# main.net
KiCad netlist of a schematic drawn in EAGLE
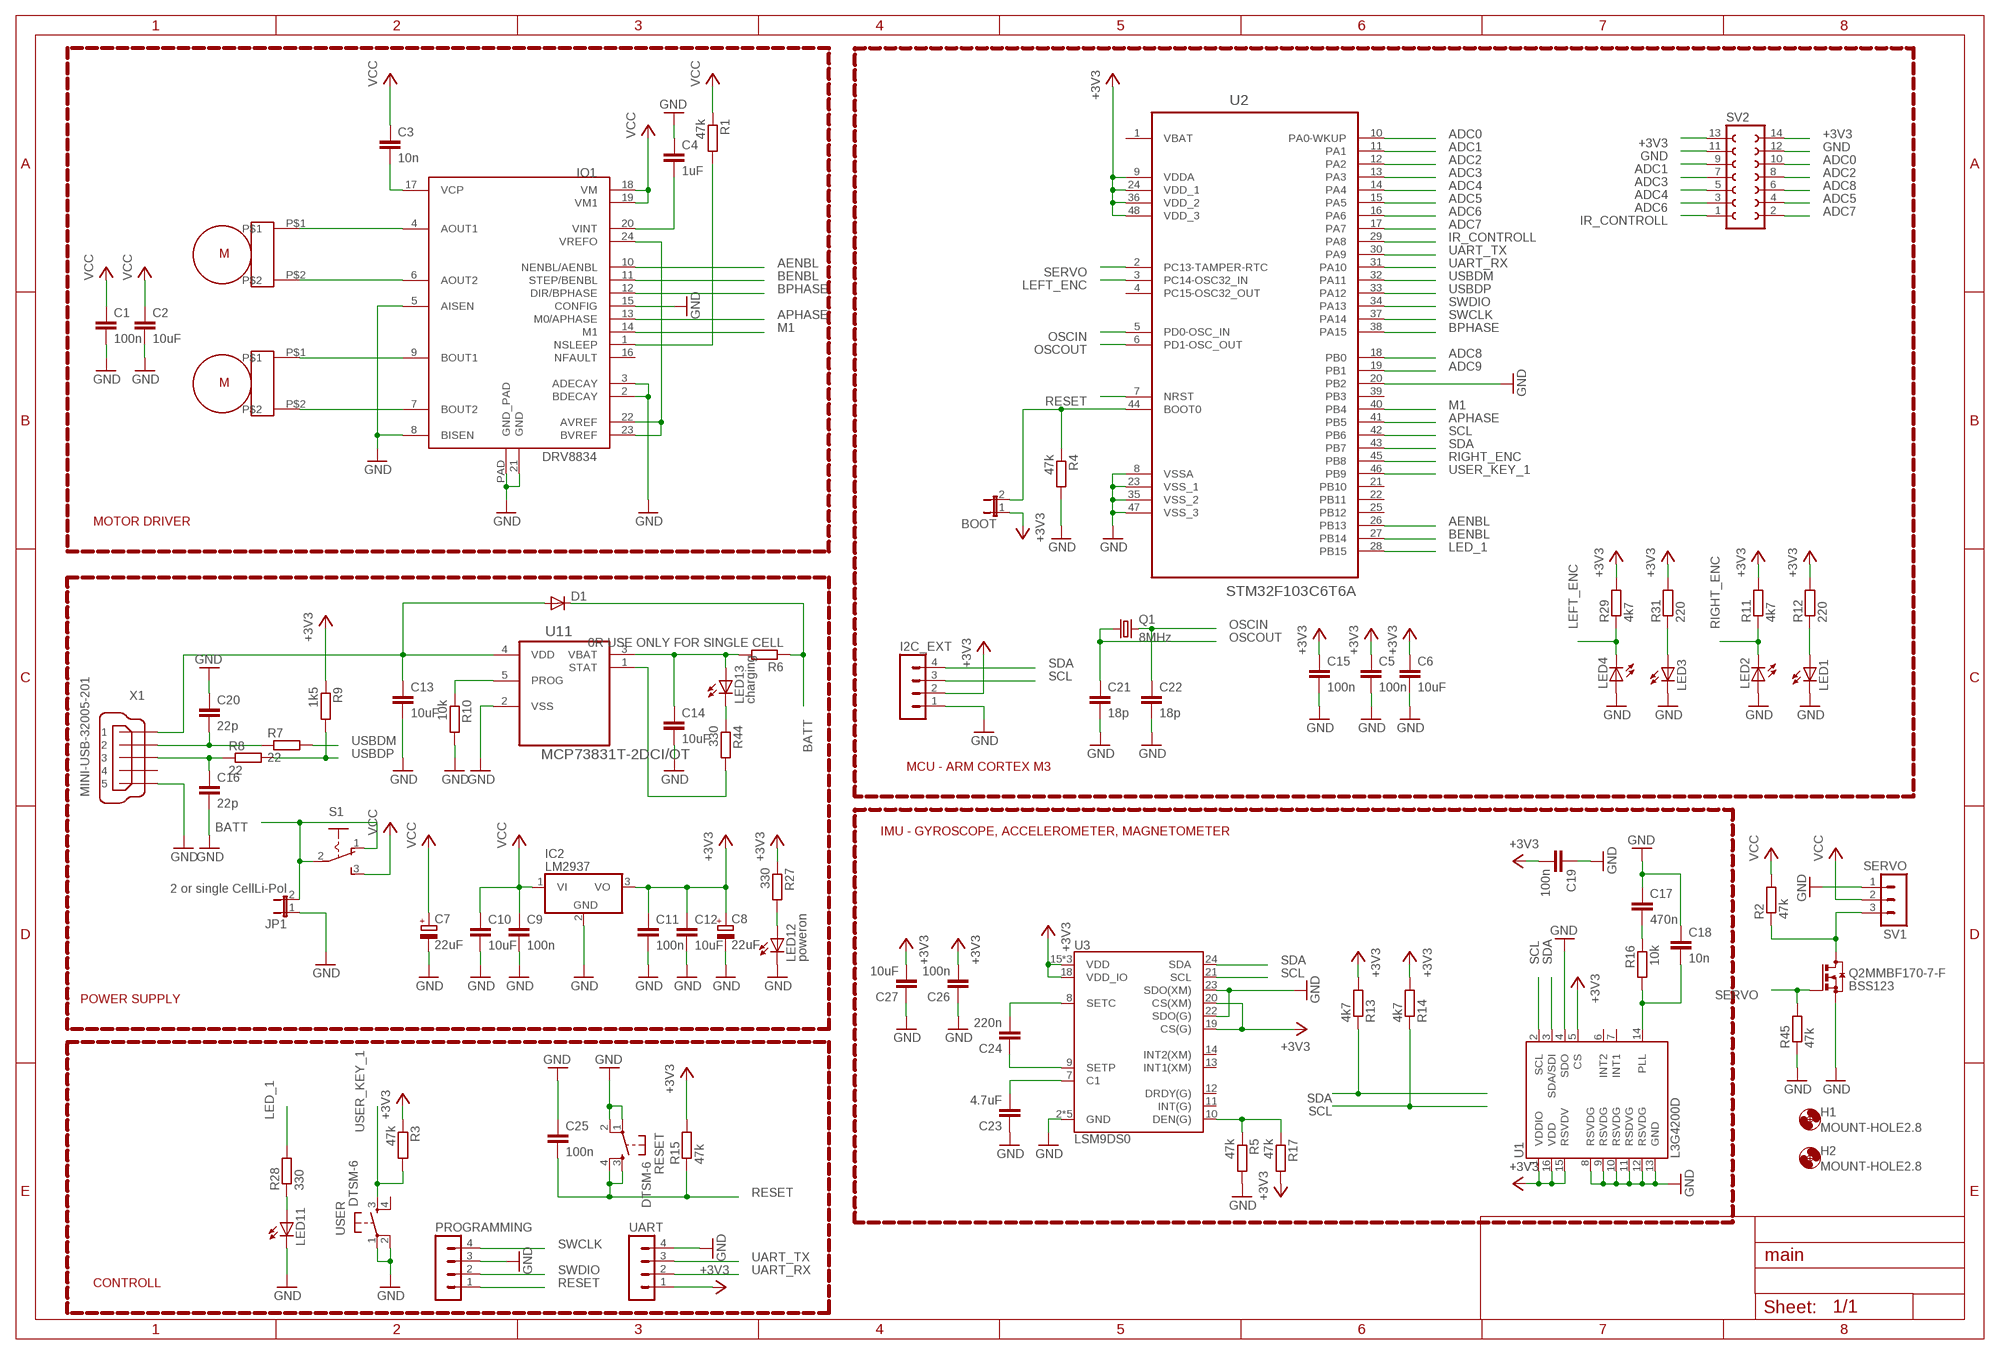
[diagram p0: schematic, sheet 1, part 1 of 2]
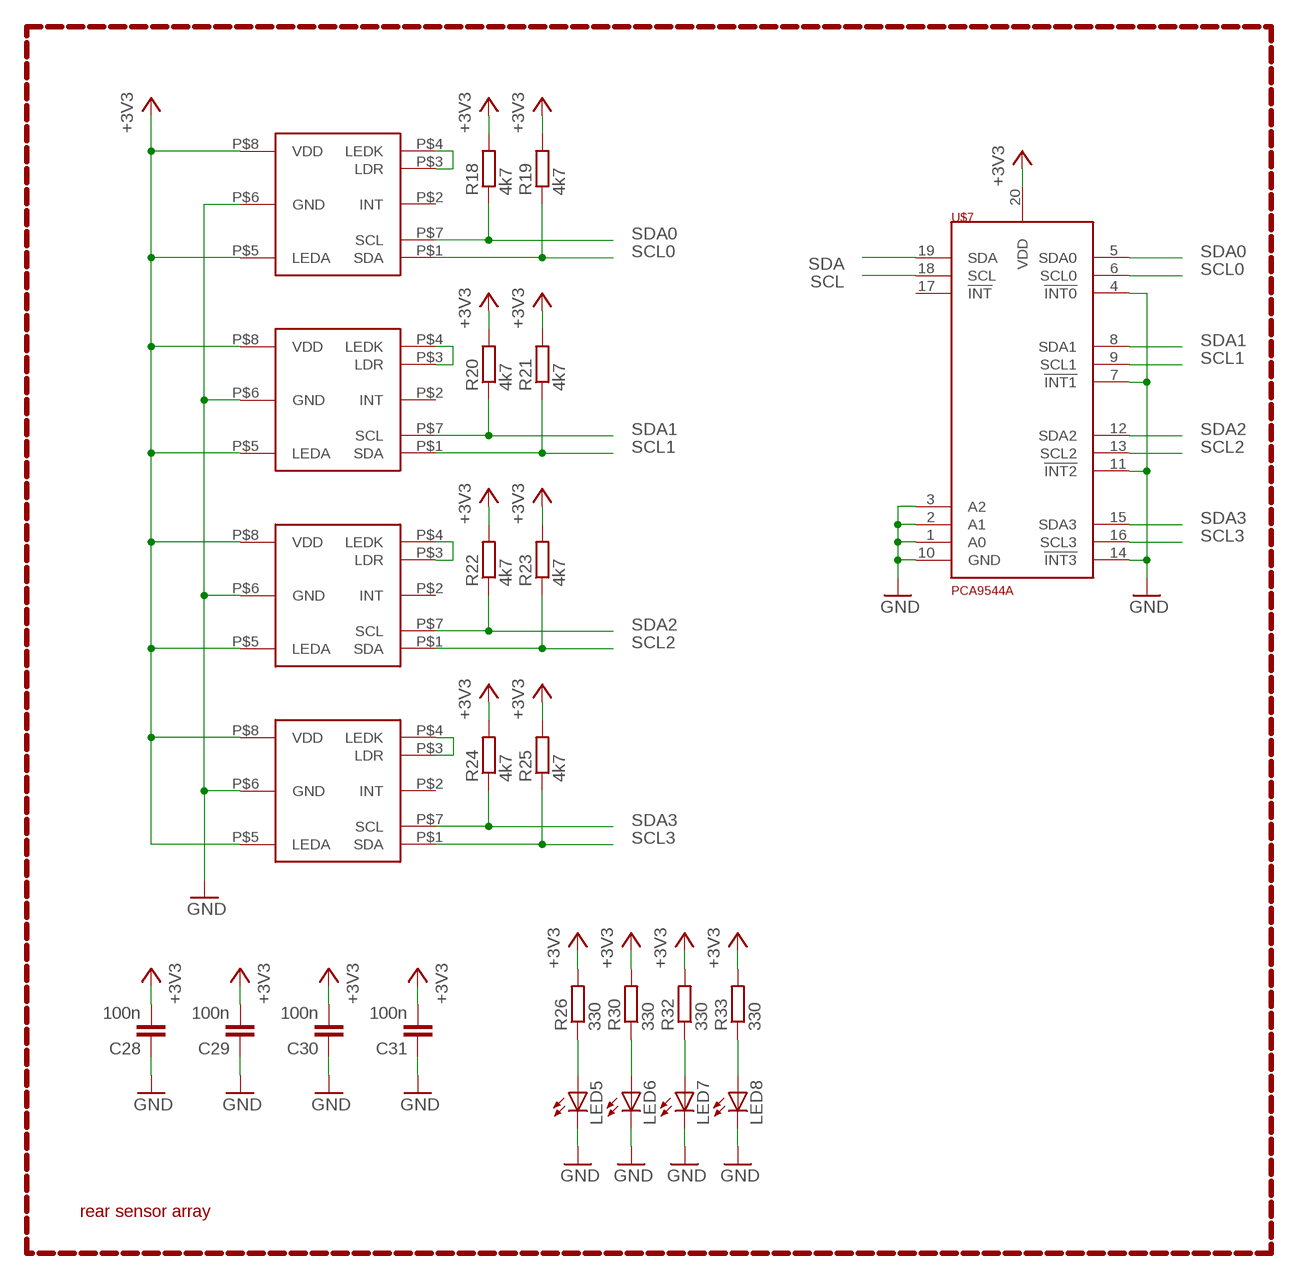
[diagram p1: schematic, sheet 1, part 2 of 2]

(export (version "E")
  (design (tool "Eeschema 10.0.6"))
  (components
    (comp (ref "BOOT")
      (value "JP1E")
      (footprint "eagle-import:JP1")
      (libsource (lib "eagle-import") (part "JP1E"))
    )
    (comp (ref "C1")
      (value "100n")
      (footprint "eagle-import:C1206")
      (libsource (lib "eagle-import") (part "C-EUC1206"))
    )
    (comp (ref "C2")
      (value "10uF")
      (footprint "eagle-import:C1206")
      (libsource (lib "eagle-import") (part "C-EUC1206"))
    )
    (comp (ref "C3")
      (value "10n")
      (footprint "eagle-import:C1206")
      (libsource (lib "eagle-import") (part "C-EUC1206"))
    )
    (comp (ref "C4")
      (value "1uF")
      (footprint "eagle-import:C1206")
      (libsource (lib "eagle-import") (part "C-EUC1206"))
    )
    (comp (ref "C5")
      (value "100n")
      (footprint "eagle-import:C0805")
      (libsource (lib "eagle-import") (part "C-EUC0805"))
    )
    (comp (ref "C6")
      (value "10uF")
      (footprint "eagle-import:C0805")
      (libsource (lib "eagle-import") (part "C-EUC0805"))
    )
    (comp (ref "C7")
      (value "22uF")
      (footprint "eagle-import:153CLV-0505")
      (libsource (lib "eagle-import") (part "CPOL-EU153CLV-0505"))
    )
    (comp (ref "C8")
      (value "22uF")
      (footprint "eagle-import:153CLV-0505")
      (libsource (lib "eagle-import") (part "CPOL-EU153CLV-0505"))
    )
    (comp (ref "C9")
      (value "100n")
      (footprint "eagle-import:C0805")
      (libsource (lib "eagle-import") (part "C-EUC0805"))
    )
    (comp (ref "C10")
      (value "10uF")
      (footprint "eagle-import:C0805")
      (libsource (lib "eagle-import") (part "C-EUC0805"))
    )
    (comp (ref "C11")
      (value "100n")
      (footprint "eagle-import:C0805")
      (libsource (lib "eagle-import") (part "C-EUC0805"))
    )
    (comp (ref "C12")
      (value "10uF")
      (footprint "eagle-import:C0805")
      (libsource (lib "eagle-import") (part "C-EUC0805"))
    )
    (comp (ref "C13")
      (value "10uF")
      (footprint "eagle-import:C0805")
      (libsource (lib "eagle-import") (part "C-EUC0805"))
    )
    (comp (ref "C14")
      (value "10uF")
      (footprint "eagle-import:C0805")
      (libsource (lib "eagle-import") (part "C-EUC0805"))
    )
    (comp (ref "C15")
      (value "100n")
      (footprint "eagle-import:C0805")
      (libsource (lib "eagle-import") (part "C-EUC0805"))
    )
    (comp (ref "C16")
      (value "22p")
      (footprint "eagle-import:C0805")
      (libsource (lib "eagle-import") (part "C-EUC0805"))
    )
    (comp (ref "C17")
      (value "470n")
      (footprint "eagle-import:C0805")
      (libsource (lib "eagle-import") (part "C-EUC0805"))
    )
    (comp (ref "C18")
      (value "10n")
      (footprint "eagle-import:C0805")
      (libsource (lib "eagle-import") (part "C-EUC0805"))
    )
    (comp (ref "C19")
      (value "100n")
      (footprint "eagle-import:C0805")
      (libsource (lib "eagle-import") (part "C-EUC0805"))
    )
    (comp (ref "C20")
      (value "22p")
      (footprint "eagle-import:C0805")
      (libsource (lib "eagle-import") (part "C-EUC0805"))
    )
    (comp (ref "C21")
      (value "18p")
      (footprint "eagle-import:C0805")
      (libsource (lib "eagle-import") (part "C-EUC0805"))
    )
    (comp (ref "C22")
      (value "18p")
      (footprint "eagle-import:C0805")
      (libsource (lib "eagle-import") (part "C-EUC0805"))
    )
    (comp (ref "C23")
      (value "4.7uF")
      (footprint "eagle-import:C0805")
      (libsource (lib "eagle-import") (part "C-EUC0805"))
    )
    (comp (ref "C24")
      (value "220n")
      (footprint "eagle-import:C0805")
      (libsource (lib "eagle-import") (part "C-EUC0805"))
    )
    (comp (ref "C25")
      (value "100n")
      (footprint "eagle-import:C0805")
      (libsource (lib "eagle-import") (part "C-EUC0805"))
    )
    (comp (ref "C26")
      (value "100n")
      (footprint "eagle-import:C0805")
      (libsource (lib "eagle-import") (part "C-EUC0805"))
    )
    (comp (ref "C27")
      (value "10uF")
      (footprint "eagle-import:C0805")
      (libsource (lib "eagle-import") (part "C-EUC0805"))
    )
    (comp (ref "C28")
      (value "100n")
      (footprint "eagle-import:C0805")
      (libsource (lib "eagle-import") (part "C-EUC0805"))
    )
    (comp (ref "C29")
      (value "100n")
      (footprint "eagle-import:C0805")
      (libsource (lib "eagle-import") (part "C-EUC0805"))
    )
    (comp (ref "C30")
      (value "100n")
      (footprint "eagle-import:C0805")
      (libsource (lib "eagle-import") (part "C-EUC0805"))
    )
    (comp (ref "C31")
      (value "100n")
      (footprint "eagle-import:C0805")
      (libsource (lib "eagle-import") (part "C-EUC0805"))
    )
    (comp (ref "D1")
      (value "DIODE-SMB")
      (footprint "eagle-import:SMB")
      (libsource (lib "eagle-import") (part "DIODE-SMB"))
    )
    (comp (ref "H1")
      (value "MOUNT-HOLE2.8")
      (footprint "eagle-import:2,8")
      (libsource (lib "eagle-import") (part "MOUNT-HOLE2.8"))
    )
    (comp (ref "H2")
      (value "MOUNT-HOLE2.8")
      (footprint "eagle-import:2,8")
      (libsource (lib "eagle-import") (part "MOUNT-HOLE2.8"))
    )
    (comp (ref "I2C_EXT")
      (value "MA04-1")
      (footprint "eagle-import:MA04-1")
      (libsource (lib "eagle-import") (part "MA04-1"))
    )
    (comp (ref "IC2")
      (value "LM2937")
      (footprint "eagle-import:TO263-3")
      (libsource (lib "eagle-import") (part "LM2937"))
    )
    (comp (ref "IO1")
      (value "DRV8834")
      (footprint "eagle-import:DRV8834_PCK")
      (libsource (lib "eagle-import") (part "DRV8834"))
    )
    (comp (ref "JP1")
      (value "2 or single CellLi-Pol")
      (footprint "eagle-import:JP1")
      (libsource (lib "eagle-import") (part "JP1E"))
    )
    (comp (ref "LED1")
      (value "LEDCHIPLED_1206")
      (footprint "eagle-import:CHIPLED_1206")
      (libsource (lib "eagle-import") (part "LEDCHIPLED_1206"))
    )
    (comp (ref "LED2")
      (value "LEDCHIPLED_1206")
      (footprint "eagle-import:CHIPLED_1206")
      (libsource (lib "eagle-import") (part "LEDCHIPLED_1206"))
    )
    (comp (ref "LED3")
      (value "LEDCHIPLED_1206")
      (footprint "eagle-import:CHIPLED_1206")
      (libsource (lib "eagle-import") (part "LEDCHIPLED_1206"))
    )
    (comp (ref "LED4")
      (value "LEDCHIPLED_1206")
      (footprint "eagle-import:CHIPLED_1206")
      (libsource (lib "eagle-import") (part "LEDCHIPLED_1206"))
    )
    (comp (ref "LED5")
      (value "LEDCHIPLED_1206")
      (footprint "eagle-import:CHIPLED_1206")
      (libsource (lib "eagle-import") (part "LEDCHIPLED_1206"))
    )
    (comp (ref "LED6")
      (value "LEDCHIPLED_1206")
      (footprint "eagle-import:CHIPLED_1206")
      (libsource (lib "eagle-import") (part "LEDCHIPLED_1206"))
    )
    (comp (ref "LED7")
      (value "LEDCHIPLED_1206")
      (footprint "eagle-import:CHIPLED_1206")
      (libsource (lib "eagle-import") (part "LEDCHIPLED_1206"))
    )
    (comp (ref "LED8")
      (value "LEDCHIPLED_1206")
      (footprint "eagle-import:CHIPLED_1206")
      (libsource (lib "eagle-import") (part "LEDCHIPLED_1206"))
    )
    (comp (ref "LED11")
      (value "LEDCHIPLED_1206")
      (footprint "eagle-import:CHIPLED_1206")
      (libsource (lib "eagle-import") (part "LEDCHIPLED_1206"))
    )
    (comp (ref "LED12")
      (value "poweron")
      (footprint "eagle-import:CHIPLED_1206")
      (libsource (lib "eagle-import") (part "LEDCHIPLED_1206"))
    )
    (comp (ref "LED13")
      (value "charging")
      (footprint "eagle-import:CHIPLED_1206")
      (libsource (lib "eagle-import") (part "LEDCHIPLED_1206"))
    )
    (comp (ref "PROGRAMMING")
      (value "MA04-1")
      (footprint "eagle-import:MA04-1")
      (libsource (lib "eagle-import") (part "MA04-1"))
    )
    (comp (ref "Q1")
      (value "8MHz")
      (footprint "eagle-import:CTS406")
      (libsource (lib "eagle-import") (part "CRYSTALCTS406"))
    )
    (comp (ref "Q2MMBF170-7-F")
      (value "BSS123")
      (footprint "eagle-import:SOT23")
      (libsource (lib "eagle-import") (part "BSS123"))
    )
    (comp (ref "R1")
      (value "47k")
      (footprint "eagle-import:M1206")
      (libsource (lib "eagle-import") (part "R-EU_M1206"))
    )
    (comp (ref "R2")
      (value "47k")
      (footprint "eagle-import:M0805")
      (libsource (lib "eagle-import") (part "R-EU_M0805"))
    )
    (comp (ref "R3")
      (value "47k")
      (footprint "eagle-import:M0805")
      (libsource (lib "eagle-import") (part "R-EU_M0805"))
    )
    (comp (ref "R4")
      (value "47k")
      (footprint "eagle-import:M0805")
      (libsource (lib "eagle-import") (part "R-EU_M0805"))
    )
    (comp (ref "R5")
      (value "47k")
      (footprint "eagle-import:M0805")
      (libsource (lib "eagle-import") (part "R-EU_M0805"))
    )
    (comp (ref "R6")
      (value "0R USE ONLY FOR SINGLE CELL")
      (footprint "eagle-import:M1206")
      (libsource (lib "eagle-import") (part "R-EU_M1206"))
    )
    (comp (ref "R7")
      (value "22")
      (footprint "eagle-import:M0805")
      (libsource (lib "eagle-import") (part "R-EU_M0805"))
    )
    (comp (ref "R8")
      (value "22")
      (footprint "eagle-import:M0805")
      (libsource (lib "eagle-import") (part "R-EU_M0805"))
    )
    (comp (ref "R9")
      (value "1k5")
      (footprint "eagle-import:M0805")
      (libsource (lib "eagle-import") (part "R-EU_M0805"))
    )
    (comp (ref "R10")
      (value "10k")
      (footprint "eagle-import:M0805")
      (libsource (lib "eagle-import") (part "R-EU_M0805"))
    )
    (comp (ref "R11")
      (value "4k7")
      (footprint "eagle-import:M0805")
      (libsource (lib "eagle-import") (part "R-EU_M0805"))
    )
    (comp (ref "R12")
      (value "220")
      (footprint "eagle-import:M0805")
      (libsource (lib "eagle-import") (part "R-EU_M0805"))
    )
    (comp (ref "R13")
      (value "4k7")
      (footprint "eagle-import:M0805")
      (libsource (lib "eagle-import") (part "R-EU_M0805"))
    )
    (comp (ref "R14")
      (value "4k7")
      (footprint "eagle-import:M0805")
      (libsource (lib "eagle-import") (part "R-EU_M0805"))
    )
    (comp (ref "R15")
      (value "47k")
      (footprint "eagle-import:M0805")
      (libsource (lib "eagle-import") (part "R-EU_M0805"))
    )
    (comp (ref "R16")
      (value "10k")
      (footprint "eagle-import:M0805")
      (libsource (lib "eagle-import") (part "R-EU_M0805"))
    )
    (comp (ref "R17")
      (value "47k")
      (footprint "eagle-import:M0805")
      (libsource (lib "eagle-import") (part "R-EU_M0805"))
    )
    (comp (ref "R18")
      (value "4k7")
      (footprint "eagle-import:M0805")
      (libsource (lib "eagle-import") (part "R-EU_M0805"))
    )
    (comp (ref "R19")
      (value "4k7")
      (footprint "eagle-import:M0805")
      (libsource (lib "eagle-import") (part "R-EU_M0805"))
    )
    (comp (ref "R20")
      (value "4k7")
      (footprint "eagle-import:M0805")
      (libsource (lib "eagle-import") (part "R-EU_M0805"))
    )
    (comp (ref "R21")
      (value "4k7")
      (footprint "eagle-import:M0805")
      (libsource (lib "eagle-import") (part "R-EU_M0805"))
    )
    (comp (ref "R22")
      (value "4k7")
      (footprint "eagle-import:M0805")
      (libsource (lib "eagle-import") (part "R-EU_M0805"))
    )
    (comp (ref "R23")
      (value "4k7")
      (footprint "eagle-import:M0805")
      (libsource (lib "eagle-import") (part "R-EU_M0805"))
    )
    (comp (ref "R24")
      (value "4k7")
      (footprint "eagle-import:M0805")
      (libsource (lib "eagle-import") (part "R-EU_M0805"))
    )
    (comp (ref "R25")
      (value "4k7")
      (footprint "eagle-import:M0805")
      (libsource (lib "eagle-import") (part "R-EU_M0805"))
    )
    (comp (ref "R26")
      (value "330")
      (footprint "eagle-import:M0805")
      (libsource (lib "eagle-import") (part "R-EU_M0805"))
    )
    (comp (ref "R27")
      (value "330")
      (footprint "eagle-import:M0805")
      (libsource (lib "eagle-import") (part "R-EU_M0805"))
    )
    (comp (ref "R28")
      (value "330")
      (footprint "eagle-import:M0805")
      (libsource (lib "eagle-import") (part "R-EU_M0805"))
    )
    (comp (ref "R29")
      (value "4k7")
      (footprint "eagle-import:M0805")
      (libsource (lib "eagle-import") (part "R-EU_M0805"))
    )
    (comp (ref "R30")
      (value "330")
      (footprint "eagle-import:M0805")
      (libsource (lib "eagle-import") (part "R-EU_M0805"))
    )
    (comp (ref "R31")
      (value "220")
      (footprint "eagle-import:M0805")
      (libsource (lib "eagle-import") (part "R-EU_M0805"))
    )
    (comp (ref "R32")
      (value "330")
      (footprint "eagle-import:M0805")
      (libsource (lib "eagle-import") (part "R-EU_M0805"))
    )
    (comp (ref "R33")
      (value "330")
      (footprint "eagle-import:M0805")
      (libsource (lib "eagle-import") (part "R-EU_M0805"))
    )
    (comp (ref "R44")
      (value "330")
      (footprint "eagle-import:M0805")
      (libsource (lib "eagle-import") (part "R-EU_M0805"))
    )
    (comp (ref "R45")
      (value "47k")
      (footprint "eagle-import:M0805")
      (libsource (lib "eagle-import") (part "R-EU_M0805"))
    )
    (comp (ref "RESET")
      (value "DTSM-6")
      (footprint "eagle-import:DTSM-6")
      (libsource (lib "eagle-import") (part "DTSM-6"))
    )
    (comp (ref "S1")
      (value "255SB")
      (footprint "eagle-import:255SB")
      (libsource (lib "eagle-import") (part "255SB"))
    )
    (comp (ref "SV1")
      (value "SERVO")
      (footprint "eagle-import:MA03-1")
      (libsource (lib "eagle-import") (part "MA03-1"))
    )
    (comp (ref "SV2")
      (value "FE07-2")
      (footprint "eagle-import:FE07-2")
      (libsource (lib "eagle-import") (part "FE07-2"))
    )
    (comp (ref "U$1")
      (value "MICRO_METAL_GEAR_MOTOR")
      (footprint "eagle-import:MICRO_METAL_GEAR_MOTOR")
      (libsource (lib "eagle-import") (part "MICRO_METAL_GEAR_MOTOR"))
    )
    (comp (ref "U$2")
      (value "MICRO_METAL_GEAR_MOTOR")
      (footprint "eagle-import:MICRO_METAL_GEAR_MOTOR")
      (libsource (lib "eagle-import") (part "MICRO_METAL_GEAR_MOTOR"))
    )
    (comp (ref "U$3")
      (value "APDS9950")
      (footprint "eagle-import:APDS9950")
      (libsource (lib "eagle-import") (part "APDS9950"))
    )
    (comp (ref "U$4")
      (value "APDS9950")
      (footprint "eagle-import:APDS9950")
      (libsource (lib "eagle-import") (part "APDS9950"))
    )
    (comp (ref "U$5")
      (value "APDS9950")
      (footprint "eagle-import:APDS9950")
      (libsource (lib "eagle-import") (part "APDS9950"))
    )
    (comp (ref "U$6")
      (value "APDS9950")
      (footprint "eagle-import:APDS9950")
      (libsource (lib "eagle-import") (part "APDS9950"))
    )
    (comp (ref "U$7")
      (value "DSSCIRCUITS_PCA9544A")
      (footprint "eagle-import:DSSCIRCUITS_TSSOP20")
      (libsource (lib "eagle-import") (part "DSSCIRCUITS_PCA9544A"))
    )
    (comp (ref "U1")
      (value "L3G4200D")
      (footprint "eagle-import:LGA16-4X4")
      (libsource (lib "eagle-import") (part "L3G4200D"))
    )
    (comp (ref "U2")
      (value "STM32F103C6T6A")
      (footprint "eagle-import:QFP50P900X900X160-48N")
      (libsource (lib "eagle-import") (part "STM32F103C6T6A"))
    )
    (comp (ref "U3")
      (value "LSM9DS0")
      (footprint "eagle-import:LGA-24")
      (libsource (lib "eagle-import") (part "LSM9DS0"))
    )
    (comp (ref "U11")
      (value "MCP73831T-2DCI/OT")
      (footprint "eagle-import:SOT95P270X145-5N")
      (libsource (lib "eagle-import") (part "MCP73831T-2DCI/OT"))
    )
    (comp (ref "UART")
      (value "MA04-1")
      (footprint "eagle-import:MA04-1")
      (libsource (lib "eagle-import") (part "MA04-1"))
    )
    (comp (ref "USER")
      (value "DTSM-6")
      (footprint "eagle-import:DTSM-6")
      (libsource (lib "eagle-import") (part "DTSM-6"))
    )
    (comp (ref "X1")
      (value "MINI-USB-32005-201")
      (footprint "eagle-import:32005-201")
      (libsource (lib "eagle-import") (part "MINI-USB-32005-201"))
    )
  )
  (nets
    (net (code "1") (name "+3V3") (class "Default")
      (node (ref "BOOT") (pin "1") (pinfunction "1_1") (pintype "passive"))
      (node (ref "C11") (pin "1") (pinfunction "1_1") (pintype "passive"))
      (node (ref "C12") (pin "1") (pinfunction "1_1") (pintype "passive"))
      (node (ref "C15") (pin "1") (pinfunction "1_1") (pintype "passive"))
      (node (ref "C19") (pin "2") (pinfunction "2_2") (pintype "passive"))
      (node (ref "C26") (pin "2") (pinfunction "2_2") (pintype "passive"))
      (node (ref "C27") (pin "2") (pinfunction "2_2") (pintype "passive"))
      (node (ref "C28") (pin "2") (pinfunction "2_2") (pintype "passive"))
      (node (ref "C29") (pin "2") (pinfunction "2_2") (pintype "passive"))
      (node (ref "C30") (pin "2") (pinfunction "2_2") (pintype "passive"))
      (node (ref "C31") (pin "2") (pinfunction "2_2") (pintype "passive"))
      (node (ref "C5") (pin "1") (pinfunction "1_1") (pintype "passive"))
      (node (ref "C6") (pin "1") (pinfunction "1_1") (pintype "passive"))
      (node (ref "C8") (pin "+") (pinfunction "+_+") (pintype "passive"))
      (node (ref "I2C_EXT") (pin "2") (pinfunction "2_2") (pintype "passive"))
      (node (ref "IC2") (pin "3") (pinfunction "VO_3") (pintype "passive"))
      (node (ref "R11") (pin "2") (pinfunction "2_2") (pintype "passive"))
      (node (ref "R12") (pin "2") (pinfunction "2_2") (pintype "passive"))
      (node (ref "R13") (pin "2") (pinfunction "2_2") (pintype "passive"))
      (node (ref "R14") (pin "2") (pinfunction "2_2") (pintype "passive"))
      (node (ref "R15") (pin "2") (pinfunction "2_2") (pintype "passive"))
      (node (ref "R17") (pin "2") (pinfunction "2_2") (pintype "passive"))
      (node (ref "R18") (pin "2") (pinfunction "2_2") (pintype "passive"))
      (node (ref "R19") (pin "2") (pinfunction "2_2") (pintype "passive"))
      (node (ref "R20") (pin "2") (pinfunction "2_2") (pintype "passive"))
      (node (ref "R21") (pin "2") (pinfunction "2_2") (pintype "passive"))
      (node (ref "R22") (pin "2") (pinfunction "2_2") (pintype "passive"))
      (node (ref "R23") (pin "2") (pinfunction "2_2") (pintype "passive"))
      (node (ref "R24") (pin "2") (pinfunction "2_2") (pintype "passive"))
      (node (ref "R25") (pin "2") (pinfunction "2_2") (pintype "passive"))
      (node (ref "R26") (pin "2") (pinfunction "2_2") (pintype "passive"))
      (node (ref "R27") (pin "1") (pinfunction "1_1") (pintype "passive"))
      (node (ref "R29") (pin "2") (pinfunction "2_2") (pintype "passive"))
      (node (ref "R3") (pin "1") (pinfunction "1_1") (pintype "passive"))
      (node (ref "R30") (pin "2") (pinfunction "2_2") (pintype "passive"))
      (node (ref "R31") (pin "2") (pinfunction "2_2") (pintype "passive"))
      (node (ref "R32") (pin "2") (pinfunction "2_2") (pintype "passive"))
      (node (ref "R33") (pin "2") (pinfunction "2_2") (pintype "passive"))
      (node (ref "R9") (pin "1") (pinfunction "1_1") (pintype "passive"))
      (node (ref "SV2") (pin "13") (pinfunction "13_13") (pintype "passive"))
      (node (ref "SV2") (pin "14") (pinfunction "14_14") (pintype "passive"))
      (node (ref "U$3") (pin "P$5") (pinfunction "LEDA_P$5") (pintype "bidirectional"))
      (node (ref "U$3") (pin "P$8") (pinfunction "VDD_P$8") (pintype "bidirectional"))
      (node (ref "U$4") (pin "P$5") (pinfunction "LEDA_P$5") (pintype "bidirectional"))
      (node (ref "U$4") (pin "P$8") (pinfunction "VDD_P$8") (pintype "bidirectional"))
      (node (ref "U$5") (pin "P$5") (pinfunction "LEDA_P$5") (pintype "bidirectional"))
      (node (ref "U$5") (pin "P$8") (pinfunction "VDD_P$8") (pintype "bidirectional"))
      (node (ref "U$6") (pin "P$5") (pinfunction "LEDA_P$5") (pintype "bidirectional"))
      (node (ref "U$6") (pin "P$8") (pinfunction "VDD_P$8") (pintype "bidirectional"))
      (node (ref "U$7") (pin "20") (pinfunction "VDD_20") (pintype "power_in"))
      (node (ref "U1") (pin "1") (pinfunction "VDDIO_1") (pintype "bidirectional"))
      (node (ref "U1") (pin "15") (pinfunction "RSVDV_15") (pintype "bidirectional"))
      (node (ref "U1") (pin "16") (pinfunction "VDD_16") (pintype "bidirectional"))
      (node (ref "U1") (pin "5") (pinfunction "CS_5") (pintype "bidirectional"))
      (node (ref "U2") (pin "24") (pinfunction "VDD_1_24") (pintype "power_in"))
      (node (ref "U2") (pin "36") (pinfunction "VDD_2_36") (pintype "power_in"))
      (node (ref "U2") (pin "48") (pinfunction "VDD_3_48") (pintype "power_in"))
      (node (ref "U2") (pin "9") (pinfunction "VDDA_9") (pintype "power_in"))
      (node (ref "U3") (pin "15") (pinfunction "VDD_15") (pintype "bidirectional"))
      (node (ref "U3") (pin "16") (pinfunction "VDD_16") (pintype "bidirectional"))
      (node (ref "U3") (pin "17") (pinfunction "VDD_17") (pintype "bidirectional"))
      (node (ref "U3") (pin "18") (pinfunction "VDD_IO_18") (pintype "bidirectional"))
      (node (ref "U3") (pin "19") (pinfunction "CS(G)_19") (pintype "bidirectional"))
      (node (ref "U3") (pin "20") (pinfunction "CS(XM)_20") (pintype "bidirectional"))
      (node (ref "UART") (pin "1") (pinfunction "1_1") (pintype "passive"))
    )
    (net (code "2") (name "/ADC0") (class "Default")
      (node (ref "SV2") (pin "10") (pinfunction "10_10") (pintype "passive"))
      (node (ref "U2") (pin "10") (pinfunction "PA0-WKUP_10") (pintype "bidirectional"))
    )
    (net (code "3") (name "/ADC1") (class "Default")
      (node (ref "SV2") (pin "9") (pinfunction "9_9") (pintype "passive"))
      (node (ref "U2") (pin "11") (pinfunction "PA1_11") (pintype "bidirectional"))
    )
    (net (code "4") (name "/ADC2") (class "Default")
      (node (ref "SV2") (pin "8") (pinfunction "8_8") (pintype "passive"))
      (node (ref "U2") (pin "12") (pinfunction "PA2_12") (pintype "bidirectional"))
    )
    (net (code "5") (name "/ADC3") (class "Default")
      (node (ref "SV2") (pin "7") (pinfunction "7_7") (pintype "passive"))
      (node (ref "U2") (pin "13") (pinfunction "PA3_13") (pintype "bidirectional"))
    )
    (net (code "6") (name "/ADC4") (class "Default")
      (node (ref "SV2") (pin "5") (pinfunction "5_5") (pintype "passive"))
      (node (ref "U2") (pin "14") (pinfunction "PA4_14") (pintype "bidirectional"))
    )
    (net (code "7") (name "/ADC5") (class "Default")
      (node (ref "SV2") (pin "4") (pinfunction "4_4") (pintype "passive"))
      (node (ref "U2") (pin "15") (pinfunction "PA5_15") (pintype "bidirectional"))
    )
    (net (code "8") (name "/ADC6") (class "Default")
      (node (ref "SV2") (pin "3") (pinfunction "3_3") (pintype "passive"))
      (node (ref "U2") (pin "16") (pinfunction "PA6_16") (pintype "bidirectional"))
    )
    (net (code "9") (name "/ADC7") (class "Default")
      (node (ref "SV2") (pin "2") (pinfunction "2_2") (pintype "passive"))
      (node (ref "U2") (pin "17") (pinfunction "PA7_17") (pintype "bidirectional"))
    )
    (net (code "10") (name "/ADC8") (class "Default")
      (node (ref "SV2") (pin "6") (pinfunction "6_6") (pintype "passive"))
      (node (ref "U2") (pin "18") (pinfunction "PB0_18") (pintype "bidirectional"))
    )
    (net (code "11") (name "/ADC9") (class "Default")
      (node (ref "U2") (pin "19") (pinfunction "PB1_19") (pintype "bidirectional"))
    )
    (net (code "12") (name "/AENBL") (class "Default")
      (node (ref "IO1") (pin "10") (pinfunction "NENBL/AENBL_10") (pintype "bidirectional"))
      (node (ref "U2") (pin "26") (pinfunction "PB13_26") (pintype "bidirectional"))
    )
    (net (code "13") (name "/APHASE") (class "Default")
      (node (ref "IO1") (pin "13") (pinfunction "M0/APHASE_13") (pintype "bidirectional"))
      (node (ref "U2") (pin "41") (pinfunction "PB5_41") (pintype "bidirectional"))
    )
    (net (code "14") (name "/BATT") (class "Default")
      (node (ref "D1") (pin "C") (pinfunction "C_C") (pintype "passive"))
      (node (ref "JP1") (pin "2") (pinfunction "2_2") (pintype "passive"))
      (node (ref "R6") (pin "1") (pinfunction "1_1") (pintype "passive"))
      (node (ref "S1") (pin "1") (pinfunction "O_1") (pintype "passive"))
      (node (ref "S1") (pin "2") (pinfunction "P_2") (pintype "passive"))
    )
    (net (code "15") (name "/BENBL") (class "Default")
      (node (ref "IO1") (pin "11") (pinfunction "STEP/BENBL_11") (pintype "bidirectional"))
      (node (ref "U2") (pin "27") (pinfunction "PB14_27") (pintype "bidirectional"))
    )
    (net (code "16") (name "/BPHASE") (class "Default")
      (node (ref "IO1") (pin "12") (pinfunction "DIR/BPHASE_12") (pintype "bidirectional"))
      (node (ref "U2") (pin "38") (pinfunction "PA15_38") (pintype "bidirectional"))
    )
    (net (code "17") (name "/IR_CONTROLL") (class "Default")
      (node (ref "SV2") (pin "1") (pinfunction "1_1") (pintype "passive"))
      (node (ref "U2") (pin "29") (pinfunction "PA8_29") (pintype "bidirectional"))
    )
    (net (code "18") (name "/LED_1") (class "Default")
      (node (ref "R28") (pin "2") (pinfunction "2_2") (pintype "passive"))
      (node (ref "U2") (pin "28") (pinfunction "PB15_28") (pintype "bidirectional"))
    )
    (net (code "19") (name "/LEFT_ENC") (class "Default")
      (node (ref "LED4") (pin "C") (pinfunction "C_C") (pintype "passive"))
      (node (ref "R29") (pin "1") (pinfunction "1_1") (pintype "passive"))
      (node (ref "U2") (pin "3") (pinfunction "PC14-OSC32_IN_3") (pintype "bidirectional"))
    )
    (net (code "20") (name "/M1") (class "Default")
      (node (ref "IO1") (pin "14") (pinfunction "M1_14") (pintype "bidirectional"))
      (node (ref "U2") (pin "40") (pinfunction "PB4_40") (pintype "bidirectional"))
    )
    (net (code "21") (name "/OSCIN") (class "Default")
      (node (ref "C22") (pin "1") (pinfunction "1_1") (pintype "passive"))
      (node (ref "Q1") (pin "3") (pinfunction "2_3") (pintype "passive"))
      (node (ref "U2") (pin "5") (pinfunction "PD0-OSC_IN_5") (pintype "bidirectional"))
    )
    (net (code "22") (name "/OSCOUT") (class "Default")
      (node (ref "C21") (pin "1") (pinfunction "1_1") (pintype "passive"))
      (node (ref "Q1") (pin "1") (pinfunction "1_1") (pintype "passive"))
      (node (ref "U2") (pin "6") (pinfunction "PD1-OSC_OUT_6") (pintype "bidirectional"))
    )
    (net (code "23") (name "/RESET") (class "Default")
      (node (ref "C25") (pin "2") (pinfunction "2_2") (pintype "passive"))
      (node (ref "PROGRAMMING") (pin "1") (pinfunction "1_1") (pintype "passive"))
      (node (ref "R15") (pin "1") (pinfunction "1_1") (pintype "passive"))
      (node (ref "RESET") (pin "3") (pinfunction "3_3") (pintype "passive"))
      (node (ref "RESET") (pin "4") (pinfunction "4_4") (pintype "passive"))
      (node (ref "U2") (pin "7") (pinfunction "NRST_7") (pintype "bidirectional"))
    )
    (net (code "24") (name "/RIGHT_ENC") (class "Default")
      (node (ref "LED2") (pin "C") (pinfunction "C_C") (pintype "passive"))
      (node (ref "R11") (pin "1") (pinfunction "1_1") (pintype "passive"))
      (node (ref "U2") (pin "45") (pinfunction "PB8_45") (pintype "bidirectional"))
    )
    (net (code "25") (name "/SCL") (class "Default")
      (node (ref "I2C_EXT") (pin "3") (pinfunction "3_3") (pintype "passive"))
      (node (ref "R14") (pin "1") (pinfunction "1_1") (pintype "passive"))
      (node (ref "U$7") (pin "18") (pinfunction "SCL_18") (pintype "bidirectional"))
      (node (ref "U1") (pin "2") (pinfunction "SCL_2") (pintype "bidirectional"))
      (node (ref "U2") (pin "42") (pinfunction "PB6_42") (pintype "bidirectional"))
      (node (ref "U3") (pin "21") (pinfunction "SCL_21") (pintype "bidirectional"))
    )
    (net (code "26") (name "/SCL0") (class "Default")
      (node (ref "R19") (pin "1") (pinfunction "1_1") (pintype "passive"))
      (node (ref "U$3") (pin "P$1") (pinfunction "SDA_P$1") (pintype "bidirectional"))
      (node (ref "U$7") (pin "6") (pinfunction "SCL0_6") (pintype "bidirectional"))
    )
    (net (code "27") (name "/SCL1") (class "Default")
      (node (ref "R21") (pin "1") (pinfunction "1_1") (pintype "passive"))
      (node (ref "U$4") (pin "P$1") (pinfunction "SDA_P$1") (pintype "bidirectional"))
      (node (ref "U$7") (pin "9") (pinfunction "SCL1_9") (pintype "bidirectional"))
    )
    (net (code "28") (name "/SCL2") (class "Default")
      (node (ref "R23") (pin "1") (pinfunction "1_1") (pintype "passive"))
      (node (ref "U$5") (pin "P$1") (pinfunction "SDA_P$1") (pintype "bidirectional"))
      (node (ref "U$7") (pin "13") (pinfunction "SCL2_13") (pintype "bidirectional"))
    )
    (net (code "29") (name "/SCL3") (class "Default")
      (node (ref "R25") (pin "1") (pinfunction "1_1") (pintype "passive"))
      (node (ref "U$6") (pin "P$1") (pinfunction "SDA_P$1") (pintype "bidirectional"))
      (node (ref "U$7") (pin "16") (pinfunction "SCL3_16") (pintype "bidirectional"))
    )
    (net (code "30") (name "/SDA") (class "Default")
      (node (ref "I2C_EXT") (pin "4") (pinfunction "4_4") (pintype "passive"))
      (node (ref "R13") (pin "1") (pinfunction "1_1") (pintype "passive"))
      (node (ref "U$7") (pin "19") (pinfunction "SDA_19") (pintype "bidirectional"))
      (node (ref "U1") (pin "3") (pinfunction "SDA/SDI_3") (pintype "bidirectional"))
      (node (ref "U2") (pin "43") (pinfunction "PB7_43") (pintype "bidirectional"))
      (node (ref "U3") (pin "24") (pinfunction "SDA_24") (pintype "bidirectional"))
    )
    (net (code "31") (name "/SDA0") (class "Default")
      (node (ref "R18") (pin "1") (pinfunction "1_1") (pintype "passive"))
      (node (ref "U$3") (pin "P$7") (pinfunction "SCL_P$7") (pintype "bidirectional"))
      (node (ref "U$7") (pin "5") (pinfunction "SDA0_5") (pintype "bidirectional"))
    )
    (net (code "32") (name "/SDA1") (class "Default")
      (node (ref "R20") (pin "1") (pinfunction "1_1") (pintype "passive"))
      (node (ref "U$4") (pin "P$7") (pinfunction "SCL_P$7") (pintype "bidirectional"))
      (node (ref "U$7") (pin "8") (pinfunction "SDA1_8") (pintype "bidirectional"))
    )
    (net (code "33") (name "/SDA2") (class "Default")
      (node (ref "R22") (pin "1") (pinfunction "1_1") (pintype "passive"))
      (node (ref "U$5") (pin "P$7") (pinfunction "SCL_P$7") (pintype "bidirectional"))
      (node (ref "U$7") (pin "12") (pinfunction "SDA2_12") (pintype "bidirectional"))
    )
    (net (code "34") (name "/SDA3") (class "Default")
      (node (ref "R24") (pin "1") (pinfunction "1_1") (pintype "passive"))
      (node (ref "U$6") (pin "P$7") (pinfunction "SCL_P$7") (pintype "bidirectional"))
      (node (ref "U$7") (pin "15") (pinfunction "SDA3_15") (pintype "bidirectional"))
    )
    (net (code "35") (name "/SERVO") (class "Default")
      (node (ref "Q2MMBF170-7-F") (pin "1") (pinfunction "G_1") (pintype "passive"))
      (node (ref "R45") (pin "2") (pinfunction "2_2") (pintype "passive"))
      (node (ref "U2") (pin "2") (pinfunction "PC13-TAMPER-RTC_2") (pintype "bidirectional"))
    )
    (net (code "36") (name "/SWCLK") (class "Default")
      (node (ref "PROGRAMMING") (pin "4") (pinfunction "4_4") (pintype "passive"))
      (node (ref "U2") (pin "37") (pinfunction "PA14_37") (pintype "bidirectional"))
    )
    (net (code "37") (name "/SWDIO") (class "Default")
      (node (ref "PROGRAMMING") (pin "2") (pinfunction "2_2") (pintype "passive"))
      (node (ref "U2") (pin "34") (pinfunction "PA13_34") (pintype "bidirectional"))
    )
    (net (code "38") (name "/UART_RX") (class "Default")
      (node (ref "U2") (pin "31") (pinfunction "PA10_31") (pintype "bidirectional"))
      (node (ref "UART") (pin "2") (pinfunction "2_2") (pintype "passive"))
    )
    (net (code "39") (name "/UART_TX") (class "Default")
      (node (ref "U2") (pin "30") (pinfunction "PA9_30") (pintype "bidirectional"))
      (node (ref "UART") (pin "3") (pinfunction "3_3") (pintype "passive"))
    )
    (net (code "40") (name "/USBDM") (class "Default")
      (node (ref "R7") (pin "2") (pinfunction "2_2") (pintype "passive"))
      (node (ref "U2") (pin "32") (pinfunction "PA11_32") (pintype "bidirectional"))
    )
    (net (code "41") (name "/USBDP") (class "Default")
      (node (ref "R8") (pin "2") (pinfunction "2_2") (pintype "passive"))
      (node (ref "R9") (pin "2") (pinfunction "2_2") (pintype "passive"))
      (node (ref "U2") (pin "33") (pinfunction "PA12_33") (pintype "bidirectional"))
    )
    (net (code "42") (name "/USER_KEY_1") (class "Default")
      (node (ref "R3") (pin "2") (pinfunction "2_2") (pintype "passive"))
      (node (ref "U2") (pin "46") (pinfunction "PB9_46") (pintype "bidirectional"))
      (node (ref "USER") (pin "3") (pinfunction "3_3") (pintype "passive"))
    )
    (net (code "43") (name "/VBAT") (class "Default")
      (node (ref "U2") (pin "1") (pinfunction "VBAT_1") (pintype "power_in"))
    )
    (net (code "44") (name "GND") (class "Default")
      (node (ref "C1") (pin "2") (pinfunction "2_2") (pintype "passive"))
      (node (ref "C10") (pin "2") (pinfunction "2_2") (pintype "passive"))
      (node (ref "C11") (pin "2") (pinfunction "2_2") (pintype "passive"))
      (node (ref "C12") (pin "2") (pinfunction "2_2") (pintype "passive"))
      (node (ref "C13") (pin "2") (pinfunction "2_2") (pintype "passive"))
      (node (ref "C14") (pin "2") (pinfunction "2_2") (pintype "passive"))
      (node (ref "C15") (pin "2") (pinfunction "2_2") (pintype "passive"))
      (node (ref "C16") (pin "2") (pinfunction "2_2") (pintype "passive"))
      (node (ref "C17") (pin "1") (pinfunction "1_1") (pintype "passive"))
      (node (ref "C18") (pin "1") (pinfunction "1_1") (pintype "passive"))
      (node (ref "C19") (pin "1") (pinfunction "1_1") (pintype "passive"))
      (node (ref "C2") (pin "2") (pinfunction "2_2") (pintype "passive"))
      (node (ref "C20") (pin "1") (pinfunction "1_1") (pintype "passive"))
      (node (ref "C21") (pin "2") (pinfunction "2_2") (pintype "passive"))
      (node (ref "C22") (pin "2") (pinfunction "2_2") (pintype "passive"))
      (node (ref "C23") (pin "1") (pinfunction "1_1") (pintype "passive"))
      (node (ref "C25") (pin "1") (pinfunction "1_1") (pintype "passive"))
      (node (ref "C26") (pin "1") (pinfunction "1_1") (pintype "passive"))
      (node (ref "C27") (pin "1") (pinfunction "1_1") (pintype "passive"))
      (node (ref "C28") (pin "1") (pinfunction "1_1") (pintype "passive"))
      (node (ref "C29") (pin "1") (pinfunction "1_1") (pintype "passive"))
      (node (ref "C30") (pin "1") (pinfunction "1_1") (pintype "passive"))
      (node (ref "C31") (pin "1") (pinfunction "1_1") (pintype "passive"))
      (node (ref "C4") (pin "1") (pinfunction "1_1") (pintype "passive"))
      (node (ref "C5") (pin "2") (pinfunction "2_2") (pintype "passive"))
      (node (ref "C6") (pin "2") (pinfunction "2_2") (pintype "passive"))
      (node (ref "C7") (pin "-") (pinfunction "-_-") (pintype "passive"))
      (node (ref "C8") (pin "-") (pinfunction "-_-") (pintype "passive"))
      (node (ref "C9") (pin "2") (pinfunction "2_2") (pintype "passive"))
      (node (ref "I2C_EXT") (pin "1") (pinfunction "1_1") (pintype "passive"))
      (node (ref "IC2") (pin "2") (pinfunction "GND_2") (pintype "passive"))
      (node (ref "IO1") (pin "15") (pinfunction "CONFIG_15") (pintype "bidirectional"))
      (node (ref "IO1") (pin "2") (pinfunction "BDECAY_2") (pintype "bidirectional"))
      (node (ref "IO1") (pin "21") (pinfunction "GND_21") (pintype "bidirectional"))
      (node (ref "IO1") (pin "3") (pinfunction "ADECAY_3") (pintype "bidirectional"))
      (node (ref "IO1") (pin "5") (pinfunction "AISEN_5") (pintype "bidirectional"))
      (node (ref "IO1") (pin "8") (pinfunction "BISEN_8") (pintype "bidirectional"))
      (node (ref "IO1") (pin "PAD") (pinfunction "GND_PAD_PAD") (pintype "bidirectional"))
      (node (ref "JP1") (pin "1") (pinfunction "1_1") (pintype "passive"))
      (node (ref "LED1") (pin "C") (pinfunction "C_C") (pintype "passive"))
      (node (ref "LED11") (pin "C") (pinfunction "C_C") (pintype "passive"))
      (node (ref "LED12") (pin "C") (pinfunction "C_C") (pintype "passive"))
      (node (ref "LED2") (pin "A") (pinfunction "A_A") (pintype "passive"))
      (node (ref "LED3") (pin "C") (pinfunction "C_C") (pintype "passive"))
      (node (ref "LED4") (pin "A") (pinfunction "A_A") (pintype "passive"))
      (node (ref "LED5") (pin "C") (pinfunction "C_C") (pintype "passive"))
      (node (ref "LED6") (pin "C") (pinfunction "C_C") (pintype "passive"))
      (node (ref "LED7") (pin "C") (pinfunction "C_C") (pintype "passive"))
      (node (ref "LED8") (pin "C") (pinfunction "C_C") (pintype "passive"))
      (node (ref "PROGRAMMING") (pin "3") (pinfunction "3_3") (pintype "passive"))
      (node (ref "Q2MMBF170-7-F") (pin "2") (pinfunction "S_2") (pintype "passive"))
      (node (ref "R10") (pin "2") (pinfunction "2_2") (pintype "passive"))
      (node (ref "R4") (pin "2") (pinfunction "2_2") (pintype "passive"))
      (node (ref "R45") (pin "1") (pinfunction "1_1") (pintype "passive"))
      (node (ref "R5") (pin "2") (pinfunction "2_2") (pintype "passive"))
      (node (ref "RESET") (pin "1") (pinfunction "1_1") (pintype "passive"))
      (node (ref "RESET") (pin "2") (pinfunction "2_2") (pintype "passive"))
      (node (ref "SV1") (pin "1") (pinfunction "1_1") (pintype "passive"))
      (node (ref "SV2") (pin "11") (pinfunction "11_11") (pintype "passive"))
      (node (ref "SV2") (pin "12") (pinfunction "12_12") (pintype "passive"))
      (node (ref "U$3") (pin "P$6") (pinfunction "GND_P$6") (pintype "bidirectional"))
      (node (ref "U$4") (pin "P$6") (pinfunction "GND_P$6") (pintype "bidirectional"))
      (node (ref "U$5") (pin "P$6") (pinfunction "GND_P$6") (pintype "bidirectional"))
      (node (ref "U$6") (pin "P$6") (pinfunction "GND_P$6") (pintype "bidirectional"))
      (node (ref "U$7") (pin "1") (pinfunction "A0_1") (pintype "input"))
      (node (ref "U$7") (pin "10") (pinfunction "GND_10") (pintype "power_in"))
      (node (ref "U$7") (pin "11") (pinfunction "~{INT2}_11") (pintype "input"))
      (node (ref "U$7") (pin "14") (pinfunction "~{INT3}_14") (pintype "input"))
      (node (ref "U$7") (pin "2") (pinfunction "A1_2") (pintype "input"))
      (node (ref "U$7") (pin "3") (pinfunction "A2_3") (pintype "input"))
      (node (ref "U$7") (pin "4") (pinfunction "~{INT0}_4") (pintype "input"))
      (node (ref "U$7") (pin "7") (pinfunction "~{INT1}_7") (pintype "input"))
      (node (ref "U1") (pin "10") (pinfunction "RSVDG_10") (pintype "bidirectional"))
      (node (ref "U1") (pin "11") (pinfunction "RSDVG_11") (pintype "bidirectional"))
      (node (ref "U1") (pin "12") (pinfunction "RSVDG_12") (pintype "bidirectional"))
      (node (ref "U1") (pin "13") (pinfunction "GND_13") (pintype "bidirectional"))
      (node (ref "U1") (pin "4") (pinfunction "SDO_4") (pintype "bidirectional"))
      (node (ref "U1") (pin "8") (pinfunction "RSVDG_8") (pintype "bidirectional"))
      (node (ref "U1") (pin "9") (pinfunction "RSVDG_9") (pintype "bidirectional"))
      (node (ref "U11") (pin "2") (pinfunction "VSS_2") (pintype "power_in"))
      (node (ref "U2") (pin "20") (pinfunction "PB2_20") (pintype "bidirectional"))
      (node (ref "U2") (pin "23") (pinfunction "VSS_1_23") (pintype "passive"))
      (node (ref "U2") (pin "35") (pinfunction "VSS_2_35") (pintype "passive"))
      (node (ref "U2") (pin "47") (pinfunction "VSS_3_47") (pintype "passive"))
      (node (ref "U2") (pin "8") (pinfunction "VSSA_8") (pintype "passive"))
      (node (ref "U3") (pin "2") (pinfunction "GND_2") (pintype "bidirectional"))
      (node (ref "U3") (pin "22") (pinfunction "SDO(G)_22") (pintype "bidirectional"))
      (node (ref "U3") (pin "23") (pinfunction "SDO(XM)_23") (pintype "bidirectional"))
      (node (ref "U3") (pin "3") (pinfunction "GND_3") (pintype "bidirectional"))
      (node (ref "U3") (pin "4") (pinfunction "GND_4") (pintype "bidirectional"))
      (node (ref "U3") (pin "5") (pinfunction "GND_5") (pintype "bidirectional"))
      (node (ref "U3") (pin "6") (pinfunction "GND_6") (pintype "bidirectional"))
      (node (ref "UART") (pin "4") (pinfunction "4_4") (pintype "passive"))
      (node (ref "USER") (pin "1") (pinfunction "1_1") (pintype "passive"))
      (node (ref "USER") (pin "2") (pinfunction "2_2") (pintype "passive"))
      (node (ref "X1") (pin "5") (pinfunction "5_5") (pintype "passive"))
    )
    (net (code "45") (name "Net-(C16-Pad1)") (class "Default")
      (node (ref "C16") (pin "1") (pinfunction "1_1") (pintype "passive"))
      (node (ref "R8") (pin "1") (pinfunction "1_1") (pintype "passive"))
      (node (ref "X1") (pin "3") (pinfunction "3_3") (pintype "passive"))
    )
    (net (code "46") (name "Net-(C17-Pad2)") (class "Default")
      (node (ref "C17") (pin "2") (pinfunction "2_2") (pintype "passive"))
      (node (ref "R16") (pin "1") (pinfunction "1_1") (pintype "passive"))
    )
    (net (code "47") (name "Net-(C20-Pad2)") (class "Default")
      (node (ref "C20") (pin "2") (pinfunction "2_2") (pintype "passive"))
      (node (ref "R7") (pin "1") (pinfunction "1_1") (pintype "passive"))
      (node (ref "X1") (pin "2") (pinfunction "2_2") (pintype "passive"))
    )
    (net (code "48") (name "Net-(IO1-AOUT1)") (class "Default")
      (node (ref "IO1") (pin "4") (pinfunction "AOUT1_4") (pintype "bidirectional"))
      (node (ref "U$1") (pin "P$1") (pinfunction "P$1_P$1") (pintype "bidirectional"))
    )
    (net (code "49") (name "Net-(IO1-AOUT2)") (class "Default")
      (node (ref "IO1") (pin "6") (pinfunction "AOUT2_6") (pintype "bidirectional"))
      (node (ref "U$1") (pin "P$2") (pinfunction "P$2_P$2") (pintype "bidirectional"))
    )
    (net (code "50") (name "Net-(IO1-AVREF)") (class "Default")
      (node (ref "IO1") (pin "22") (pinfunction "AVREF_22") (pintype "bidirectional"))
      (node (ref "IO1") (pin "23") (pinfunction "BVREF_23") (pintype "bidirectional"))
      (node (ref "IO1") (pin "24") (pinfunction "VREFO_24") (pintype "bidirectional"))
    )
    (net (code "51") (name "Net-(IO1-BOUT1)") (class "Default")
      (node (ref "IO1") (pin "9") (pinfunction "BOUT1_9") (pintype "bidirectional"))
      (node (ref "U$2") (pin "P$1") (pinfunction "P$1_P$1") (pintype "bidirectional"))
    )
    (net (code "52") (name "Net-(IO1-BOUT2)") (class "Default")
      (node (ref "IO1") (pin "7") (pinfunction "BOUT2_7") (pintype "bidirectional"))
      (node (ref "U$2") (pin "P$2") (pinfunction "P$2_P$2") (pintype "bidirectional"))
    )
    (net (code "53") (name "Net-(IO1-NSLEEP)") (class "Default")
      (node (ref "IO1") (pin "1") (pinfunction "NSLEEP_1") (pintype "bidirectional"))
      (node (ref "R1") (pin "2") (pinfunction "2_2") (pintype "passive"))
    )
    (net (code "54") (name "Net-(IO1-VCP)") (class "Default")
      (node (ref "C3") (pin "2") (pinfunction "2_2") (pintype "passive"))
      (node (ref "IO1") (pin "17") (pinfunction "VCP_17") (pintype "bidirectional"))
    )
    (net (code "55") (name "Net-(IO1-VINT)") (class "Default")
      (node (ref "C4") (pin "2") (pinfunction "2_2") (pintype "passive"))
      (node (ref "IO1") (pin "20") (pinfunction "VINT_20") (pintype "bidirectional"))
    )
    (net (code "56") (name "Net-(LED1-PadA)") (class "Default")
      (node (ref "LED1") (pin "A") (pinfunction "A_A") (pintype "passive"))
      (node (ref "R12") (pin "1") (pinfunction "1_1") (pintype "passive"))
    )
    (net (code "57") (name "Net-(LED3-PadA)") (class "Default")
      (node (ref "LED3") (pin "A") (pinfunction "A_A") (pintype "passive"))
      (node (ref "R31") (pin "1") (pinfunction "1_1") (pintype "passive"))
    )
    (net (code "58") (name "Net-(LED5-PadA)") (class "Default")
      (node (ref "LED5") (pin "A") (pinfunction "A_A") (pintype "passive"))
      (node (ref "R26") (pin "1") (pinfunction "1_1") (pintype "passive"))
    )
    (net (code "59") (name "Net-(LED6-PadA)") (class "Default")
      (node (ref "LED6") (pin "A") (pinfunction "A_A") (pintype "passive"))
      (node (ref "R30") (pin "1") (pinfunction "1_1") (pintype "passive"))
    )
    (net (code "60") (name "Net-(LED7-PadA)") (class "Default")
      (node (ref "LED7") (pin "A") (pinfunction "A_A") (pintype "passive"))
      (node (ref "R32") (pin "1") (pinfunction "1_1") (pintype "passive"))
    )
    (net (code "61") (name "Net-(LED8-PadA)") (class "Default")
      (node (ref "LED8") (pin "A") (pinfunction "A_A") (pintype "passive"))
      (node (ref "R33") (pin "1") (pinfunction "1_1") (pintype "passive"))
    )
    (net (code "62") (name "Net-(LED11-PadA)") (class "Default")
      (node (ref "LED11") (pin "A") (pinfunction "A_A") (pintype "passive"))
      (node (ref "R28") (pin "1") (pinfunction "1_1") (pintype "passive"))
    )
    (net (code "63") (name "Net-(LED12-PadA)") (class "Default")
      (node (ref "LED12") (pin "A") (pinfunction "A_A") (pintype "passive"))
      (node (ref "R27") (pin "2") (pinfunction "2_2") (pintype "passive"))
    )
    (net (code "64") (name "Net-(LED13-PadC)") (class "Default")
      (node (ref "LED13") (pin "C") (pinfunction "C_C") (pintype "passive"))
      (node (ref "R44") (pin "1") (pinfunction "1_1") (pintype "passive"))
    )
    (net (code "65") (name "Net-(Q2MMBF170-7-F-D)") (class "Default")
      (node (ref "Q2MMBF170-7-F") (pin "3") (pinfunction "D_3") (pintype "passive"))
      (node (ref "R2") (pin "1") (pinfunction "1_1") (pintype "passive"))
      (node (ref "SV1") (pin "3") (pinfunction "3_3") (pintype "passive"))
    )
    (net (code "66") (name "Net-(U$3-LDR)") (class "Default")
      (node (ref "U$3") (pin "P$3") (pinfunction "LDR_P$3") (pintype "bidirectional"))
      (node (ref "U$3") (pin "P$4") (pinfunction "LEDK_P$4") (pintype "bidirectional"))
    )
    (net (code "67") (name "Net-(U$4-LDR)") (class "Default")
      (node (ref "U$4") (pin "P$3") (pinfunction "LDR_P$3") (pintype "bidirectional"))
      (node (ref "U$4") (pin "P$4") (pinfunction "LEDK_P$4") (pintype "bidirectional"))
    )
    (net (code "68") (name "Net-(U$5-LDR)") (class "Default")
      (node (ref "U$5") (pin "P$3") (pinfunction "LDR_P$3") (pintype "bidirectional"))
      (node (ref "U$5") (pin "P$4") (pinfunction "LEDK_P$4") (pintype "bidirectional"))
    )
    (net (code "69") (name "Net-(U$6-LDR)") (class "Default")
      (node (ref "U$6") (pin "P$3") (pinfunction "LDR_P$3") (pintype "bidirectional"))
      (node (ref "U$6") (pin "P$4") (pinfunction "LEDK_P$4") (pintype "bidirectional"))
    )
    (net (code "70") (name "Net-(U1-PLL)") (class "Default")
      (node (ref "C18") (pin "2") (pinfunction "2_2") (pintype "passive"))
      (node (ref "R16") (pin "2") (pinfunction "2_2") (pintype "passive"))
      (node (ref "U1") (pin "14") (pinfunction "PLL_14") (pintype "bidirectional"))
    )
    (net (code "71") (name "Net-(U2-BOOT0)") (class "Default")
      (node (ref "BOOT") (pin "2") (pinfunction "2_2") (pintype "passive"))
      (node (ref "R4") (pin "1") (pinfunction "1_1") (pintype "passive"))
      (node (ref "U2") (pin "44") (pinfunction "BOOT0_44") (pintype "input"))
    )
    (net (code "72") (name "Net-(U3-C1)") (class "Default")
      (node (ref "C23") (pin "2") (pinfunction "2_2") (pintype "passive"))
      (node (ref "U3") (pin "7") (pinfunction "C1_7") (pintype "bidirectional"))
    )
    (net (code "73") (name "Net-(U3-DEN(G))") (class "Default")
      (node (ref "R17") (pin "1") (pinfunction "1_1") (pintype "passive"))
      (node (ref "R5") (pin "1") (pinfunction "1_1") (pintype "passive"))
      (node (ref "U3") (pin "10") (pinfunction "DEN(G)_10") (pintype "bidirectional"))
    )
    (net (code "74") (name "Net-(U3-SETC)") (class "Default")
      (node (ref "C24") (pin "2") (pinfunction "2_2") (pintype "passive"))
      (node (ref "U3") (pin "8") (pinfunction "SETC_8") (pintype "bidirectional"))
    )
    (net (code "75") (name "Net-(U3-SETP)") (class "Default")
      (node (ref "C24") (pin "1") (pinfunction "1_1") (pintype "passive"))
      (node (ref "U3") (pin "9") (pinfunction "SETP_9") (pintype "bidirectional"))
    )
    (net (code "76") (name "Net-(U11-PROG)") (class "Default")
      (node (ref "R10") (pin "1") (pinfunction "1_1") (pintype "passive"))
      (node (ref "U11") (pin "5") (pinfunction "PROG_5") (pintype "input"))
    )
    (net (code "77") (name "Net-(U11-STAT)") (class "Default")
      (node (ref "R44") (pin "2") (pinfunction "2_2") (pintype "passive"))
      (node (ref "U11") (pin "1") (pinfunction "STAT_1") (pintype "output"))
    )
    (net (code "78") (name "Net-(U11-VBAT)") (class "Default")
      (node (ref "C14") (pin "1") (pinfunction "1_1") (pintype "passive"))
      (node (ref "LED13") (pin "A") (pinfunction "A_A") (pintype "passive"))
      (node (ref "R6") (pin "2") (pinfunction "2_2") (pintype "passive"))
      (node (ref "U11") (pin "3") (pinfunction "VBAT_3") (pintype "power_in"))
    )
    (net (code "79") (name "Net-(U11-VDD)") (class "Default")
      (node (ref "C13") (pin "1") (pinfunction "1_1") (pintype "passive"))
      (node (ref "D1") (pin "A") (pinfunction "A_A") (pintype "passive"))
      (node (ref "U11") (pin "4") (pinfunction "VDD_4") (pintype "power_in"))
      (node (ref "X1") (pin "1") (pinfunction "1_1") (pintype "passive"))
    )
    (net (code "80") (name "VCC") (class "Default")
      (node (ref "C1") (pin "1") (pinfunction "1_1") (pintype "passive"))
      (node (ref "C10") (pin "1") (pinfunction "1_1") (pintype "passive"))
      (node (ref "C2") (pin "1") (pinfunction "1_1") (pintype "passive"))
      (node (ref "C3") (pin "1") (pinfunction "1_1") (pintype "passive"))
      (node (ref "C7") (pin "+") (pinfunction "+_+") (pintype "passive"))
      (node (ref "C9") (pin "1") (pinfunction "1_1") (pintype "passive"))
      (node (ref "IC2") (pin "1") (pinfunction "VI_1") (pintype "input"))
      (node (ref "IO1") (pin "18") (pinfunction "VM_18") (pintype "bidirectional"))
      (node (ref "IO1") (pin "19") (pinfunction "VM1_19") (pintype "bidirectional"))
      (node (ref "R1") (pin "1") (pinfunction "1_1") (pintype "passive"))
      (node (ref "R2") (pin "2") (pinfunction "2_2") (pintype "passive"))
      (node (ref "S1") (pin "3") (pinfunction "S_3") (pintype "passive"))
      (node (ref "SV1") (pin "2") (pinfunction "2_2") (pintype "passive"))
    )
    (net (code "81") (name "unconnected-(IO1-NFAULT-Pad16)") (class "Default")
      (node (ref "IO1") (pin "16") (pinfunction "NFAULT_16") (pintype "bidirectional"))
    )
    (net (code "82") (name "unconnected-(U$3-INT-PadP$2)") (class "Default")
      (node (ref "U$3") (pin "P$2") (pinfunction "INT_P$2") (pintype "bidirectional"))
    )
    (net (code "83") (name "unconnected-(U$4-INT-PadP$2)") (class "Default")
      (node (ref "U$4") (pin "P$2") (pinfunction "INT_P$2") (pintype "bidirectional"))
    )
    (net (code "84") (name "unconnected-(U$5-INT-PadP$2)") (class "Default")
      (node (ref "U$5") (pin "P$2") (pinfunction "INT_P$2") (pintype "bidirectional"))
    )
    (net (code "85") (name "unconnected-(U$6-INT-PadP$2)") (class "Default")
      (node (ref "U$6") (pin "P$2") (pinfunction "INT_P$2") (pintype "bidirectional"))
    )
    (net (code "86") (name "unconnected-(U$7-~{INT}-Pad17)") (class "Default")
      (node (ref "U$7") (pin "17") (pinfunction "~{INT}_17") (pintype "output"))
    )
    (net (code "87") (name "unconnected-(U1-INT1-Pad7)") (class "Default")
      (node (ref "U1") (pin "7") (pinfunction "INT1_7") (pintype "bidirectional"))
    )
    (net (code "88") (name "unconnected-(U1-INT2-Pad6)") (class "Default")
      (node (ref "U1") (pin "6") (pinfunction "INT2_6") (pintype "bidirectional"))
    )
    (net (code "89") (name "unconnected-(U2-PB3-Pad39)") (class "Default")
      (node (ref "U2") (pin "39") (pinfunction "PB3_39") (pintype "bidirectional"))
    )
    (net (code "90") (name "unconnected-(U2-PB10-Pad21)") (class "Default")
      (node (ref "U2") (pin "21") (pinfunction "PB10_21") (pintype "bidirectional"))
    )
    (net (code "91") (name "unconnected-(U2-PB11-Pad22)") (class "Default")
      (node (ref "U2") (pin "22") (pinfunction "PB11_22") (pintype "bidirectional"))
    )
    (net (code "92") (name "unconnected-(U2-PB12-Pad25)") (class "Default")
      (node (ref "U2") (pin "25") (pinfunction "PB12_25") (pintype "bidirectional"))
    )
    (net (code "93") (name "unconnected-(U2-PC15-OSC32_OUT-Pad4)") (class "Default")
      (node (ref "U2") (pin "4") (pinfunction "PC15-OSC32_OUT_4") (pintype "bidirectional"))
    )
    (net (code "94") (name "unconnected-(U3-DRDY(G)-Pad12)") (class "Default")
      (node (ref "U3") (pin "12") (pinfunction "DRDY(G)_12") (pintype "bidirectional"))
    )
    (net (code "95") (name "unconnected-(U3-INT(G)-Pad11)") (class "Default")
      (node (ref "U3") (pin "11") (pinfunction "INT(G)_11") (pintype "bidirectional"))
    )
    (net (code "96") (name "unconnected-(U3-INT1(XM)-Pad13)") (class "Default")
      (node (ref "U3") (pin "13") (pinfunction "INT1(XM)_13") (pintype "bidirectional"))
    )
    (net (code "97") (name "unconnected-(U3-INT2(XM)-Pad14)") (class "Default")
      (node (ref "U3") (pin "14") (pinfunction "INT2(XM)_14") (pintype "bidirectional"))
    )
    (net (code "98") (name "unconnected-(USER-Pad4)") (class "Default")
      (node (ref "USER") (pin "4") (pinfunction "4_4") (pintype "passive"))
    )
    (net (code "99") (name "unconnected-(X1-Pad4)") (class "Default")
      (node (ref "X1") (pin "4") (pinfunction "4_4") (pintype "passive"))
    )
  )
)
